# DAU-3Phase-PSU.net
KiCad netlist of a schematic drawn in Altium Designer
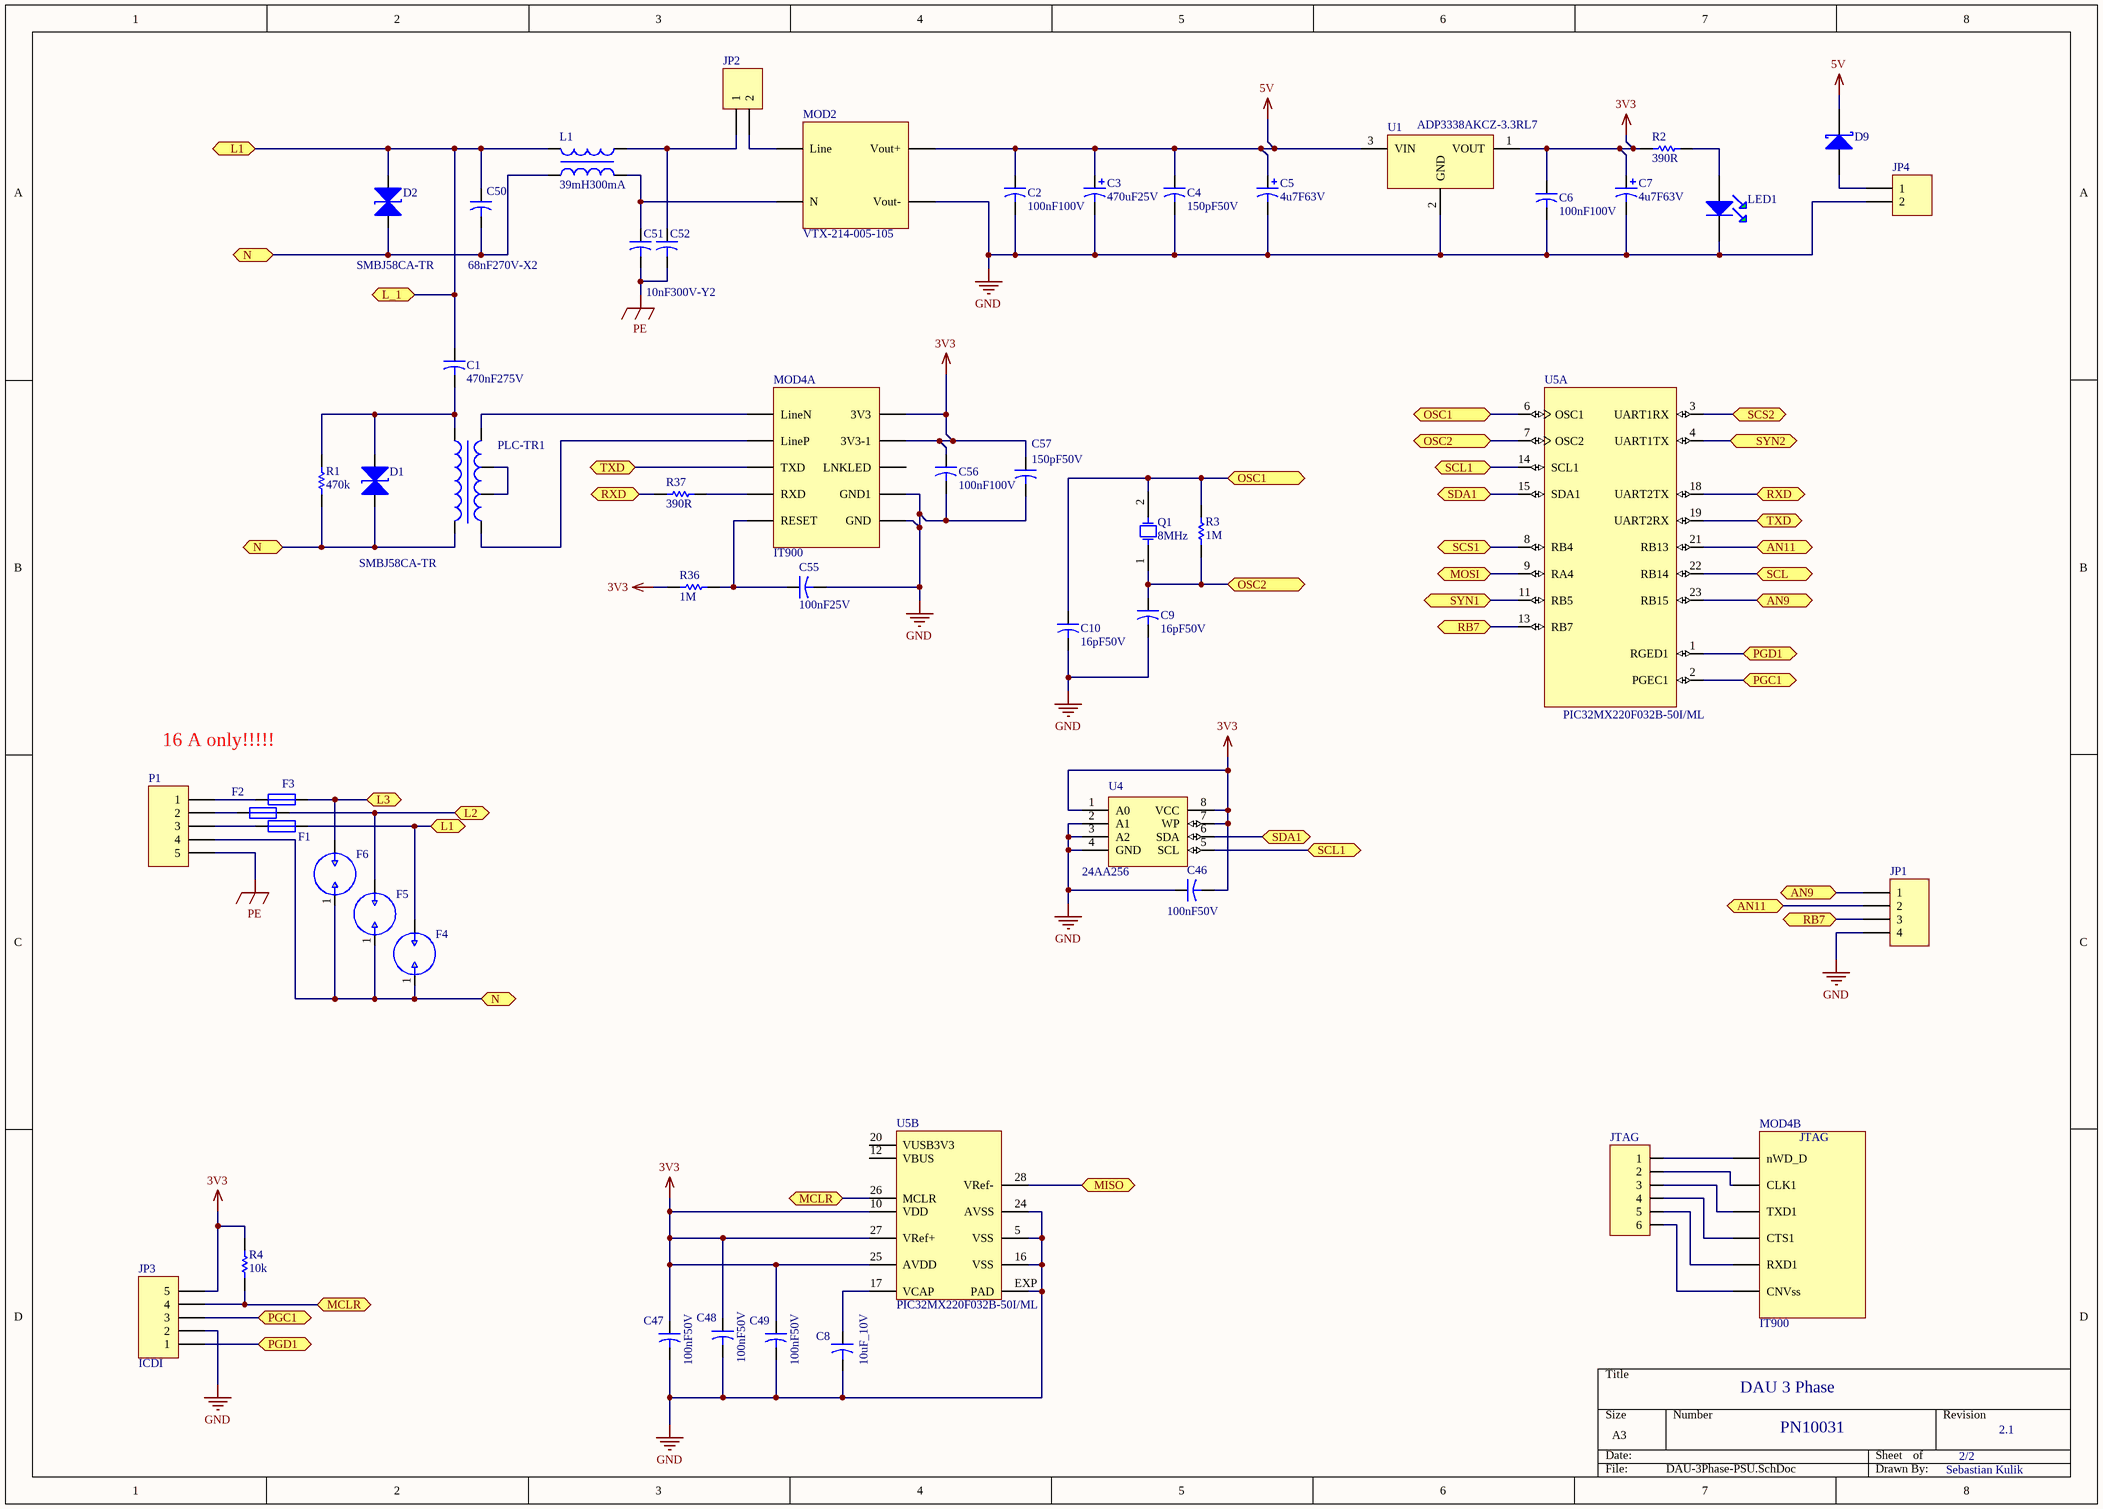
[diagram p0: DAU-3Phase-PSU.SchDoc]

(export (version "E")
  (design (tool "Eeschema 10.0.6"))
  (components
    (comp (ref "C1")
      (value "470nF275V")
      (footprint "C150-072X183")
      (description "X2, PP")
      (fields (field (name "MANUFACTURER") "WE") (field (name "PUBLISHER") "Sebastian Kulik"))
      (libsource (lib "Capacitors") (part "470nF275V"))
    )
    (comp (ref "C2")
      (value "100nF100V")
      (footprint "C0805")
      (description "AVX, X7R, 5%, 100V")
      (fields
        (field (name "MANUFACTURER") "AVX")
        (field (name "Comment") "100nF100V_0805")
        (field (name "PUBLISHER") "Sebastian Kulik")
      )
      (libsource (lib "Capacitors") (part "100nF100V_0805"))
    )
    (comp (ref "C3")
      (value "470uF25V")
      (footprint "Panasonic-FT-F_Case")
      (description "Panasonic, FT series")
      (fields
        (field (name "MANUFACTURER") "Panasonic")
        (field (name "Comment") "470uF25V_POL_FT")
        (field (name "PUBLISHER") "Sebastian Kulik")
      )
      (libsource (lib "Capacitors") (part "470uF25V_POL_FT"))
    )
    (comp (ref "C4")
      (value "150pF50V")
      (footprint "C0402")
      (description "C series, 5%, 50V")
      (fields
        (field (name "MANUFACTURER") "Murata")
        (field (name "Comment") "150p50V_0402")
        (field (name "PUBLISHER") "Sebastian Kulik")
      )
      (libsource (lib "") (part "150p50V_0402_1"))
    )
    (comp (ref "C5")
      (value "4u7F63V")
      (footprint "Panasonic-FT-C_Case")
      (description "Panasonic, TK series")
      (fields
        (field (name "MANUFACTURER") "Panasonic")
        (field (name "Comment") "4u7F25V_POL_TK")
        (field (name "PUBLISHER") "Sebastian Kulik")
      )
      (libsource (lib "Capacitors") (part "4u7F25V_POL_TK"))
    )
    (comp (ref "C6")
      (value "100nF100V")
      (footprint "C0805")
      (description "AVX, X7R, 5%, 100V")
      (fields
        (field (name "MANUFACTURER") "AVX")
        (field (name "Comment") "100nF100V_0805")
        (field (name "PUBLISHER") "Sebastian Kulik")
      )
      (libsource (lib "") (part "100nF100V_0805_1"))
    )
    (comp (ref "C7")
      (value "4u7F63V")
      (footprint "Panasonic-FT-C_Case")
      (description "Panasonic, TK series")
      (fields
        (field (name "MANUFACTURER") "Panasonic")
        (field (name "Comment") "4u7F25V_POL_TK")
        (field (name "PUBLISHER") "Sebastian Kulik")
      )
      (libsource (lib "Capacitors") (part "4u7F25V_POL_TK"))
    )
    (comp (ref "C8")
      (value "10uF_10V")
      (footprint "C0603")
      (description "AVX ,  X5R, 20%, 10V")
      (fields
        (field (name "MANUFACTURER") "AVX")
        (field (name "Comment") "10uF10V_0603")
        (field (name "PUBLISHER") "Sebastian Kulik")
      )
      (libsource (lib "Capacitors") (part "10uF10V_0603"))
    )
    (comp (ref "C9")
      (value "16pF50V")
      (footprint "C0402")
      (description "C series, 5%, 50V")
      (fields
        (field (name "MANUFACTURER") "Kemet")
        (field (name "Comment") "16pF50V_0402")
        (field (name "PUBLISHER") "Sebastian Kulik")
      )
      (libsource (lib "Capacitors") (part "16pF50V_0402"))
    )
    (comp (ref "C10")
      (value "16pF50V")
      (footprint "C0402")
      (description "C series, 5%, 50V")
      (fields
        (field (name "MANUFACTURER") "Kemet")
        (field (name "Comment") "16pF50V_0402")
        (field (name "PUBLISHER") "Sebastian Kulik")
      )
      (libsource (lib "Capacitors") (part "16pF50V_0402"))
    )
    (comp (ref "C46")
      (value "100nF50V")
      (footprint "C0402")
      (description "C series, X5R, 10%, 50V")
      (fields
        (field (name "MANUFACTURER") "Murata")
        (field (name "Comment") "100n50V_0402")
        (field (name "PUBLISHER") "Sebastian Kulik")
      )
      (libsource (lib "Capacitors") (part "100n50V_0402"))
    )
    (comp (ref "C47")
      (value "100nF50V")
      (footprint "C0402")
      (description "C series, X5R, 10%, 50V")
      (fields
        (field (name "MANUFACTURER") "Murata")
        (field (name "Comment") "100n50V_0402")
        (field (name "PUBLISHER") "Sebastian Kulik")
      )
      (libsource (lib "Capacitors") (part "100n50V_0402"))
    )
    (comp (ref "C48")
      (value "100nF50V")
      (footprint "C0402")
      (description "C series, X5R, 10%, 50V")
      (fields
        (field (name "MANUFACTURER") "Murata")
        (field (name "Comment") "100n50V_0402")
        (field (name "PUBLISHER") "Sebastian Kulik")
      )
      (libsource (lib "Capacitors") (part "100n50V_0402"))
    )
    (comp (ref "C49")
      (value "100nF50V")
      (footprint "C0402")
      (description "C series, X5R, 10%, 50V")
      (fields
        (field (name "MANUFACTURER") "Murata")
        (field (name "Comment") "100n50V_0402")
        (field (name "PUBLISHER") "Sebastian Kulik")
      )
      (libsource (lib "Capacitors") (part "100n50V_0402"))
    )
    (comp (ref "C50")
      (value "68nF270V-X2")
      (footprint "Foil-7,5x10")
      (description "X2 capacitor")
      (fields (field (name "MANUFACTURER") "WE") (field (name "PUBLISHER") "Sebastian Kulik"))
      (libsource (lib "Capacitors") (part "68nF270V-X2"))
    )
    (comp (ref "C51")
      (value "10nF300V-Y2")
      (footprint "Foil-10x13")
      (description "Y2 capacitor")
      (fields (field (name "MANUFACTURER") "EPCOS") (field (name "PUBLISHER") "Sebastian Kulik"))
      (libsource (lib "Capacitors") (part "10nF300V-Y2"))
    )
    (comp (ref "C52")
      (value "10nF300V-Y2")
      (footprint "Foil-10x13")
      (description "Y2 capacitor")
      (fields (field (name "MANUFACTURER") "EPCOS") (field (name "PUBLISHER") "Sebastian Kulik"))
      (libsource (lib "Capacitors") (part "10nF300V-Y2"))
    )
    (comp (ref "C55")
      (value "100nF25V")
      (footprint "C0402")
      (description "AVX, X5R, 10%, 25V")
      (fields
        (field (name "MANUFACTURER") "AVX")
        (field (name "Comment") "100nF25V_0402")
        (field (name "PUBLISHER") "Sebastian Kulik")
      )
      (libsource (lib "Capacitors") (part "100nF25V_0402"))
    )
    (comp (ref "C56")
      (value "100nF100V")
      (footprint "C0805")
      (description "AVX, X7R, 5%, 100V")
      (fields
        (field (name "MANUFACTURER") "AVX")
        (field (name "Comment") "100nF100V_0805")
        (field (name "PUBLISHER") "Sebastian Kulik")
      )
      (libsource (lib "") (part "100nF100V_0805_1"))
    )
    (comp (ref "C57")
      (value "150pF50V")
      (footprint "C0402")
      (description "C series, 5%, 50V")
      (fields
        (field (name "MANUFACTURER") "Murata")
        (field (name "Comment") "150p50V_0402")
        (field (name "PUBLISHER") "Sebastian Kulik")
      )
      (libsource (lib "Capacitors") (part "150p50V_0402"))
    )
    (comp (ref "D1")
      (value "SMBJ58CA-TR")
      (footprint "SMB")
      (description "Transient voltage suppressor, 600W")
      (fields (field (name "MANUFACTURER") "STMicro") (field (name "PUBLISHER") "Sebastian Kulik"))
      (libsource (lib "") (part "SMBJ58CA-TR_1"))
    )
    (comp (ref "D2")
      (value "SMBJ58CA-TR")
      (footprint "SMB")
      (description "Transient voltage suppressor, 600W")
      (fields (field (name "MANUFACTURER") "STMicro") (field (name "PUBLISHER") "Sebastian Kulik"))
      (libsource (lib "Discrete") (part "SMBJ58CA-TR"))
    )
    (comp (ref "D9")
      (value "RB160M-30TR")
      (footprint "SOD123")
      (description "Diode Schottky,2A,40V")
      (fields (field (name "MANUFACTURER") "Rohm") (field (name "PUBLISHER") "Sebastian Kulik"))
      (libsource (lib "Discrete") (part "RB160M-30TR"))
    )
    (comp (ref "F1")
      (value "MCMET 250MA 250V")
      (footprint "TR5")
      (fields (field (name "MANUFACTURER") "Multicomp") (field (name "PUBLISHER") "Sebastian Kulik"))
      (libsource (lib "Mechanical") (part "MCMET 250MA 250V"))
    )
    (comp (ref "F2")
      (value "MCMET 250MA 250V")
      (footprint "TR5")
      (fields (field (name "MANUFACTURER") "Multicomp") (field (name "PUBLISHER") "Sebastian Kulik"))
      (libsource (lib "Mechanical") (part "MCMET 250MA 250V"))
    )
    (comp (ref "F3")
      (value "MCMET 250MA 250V")
      (footprint "TR5")
      (fields (field (name "MANUFACTURER") "Multicomp") (field (name "PUBLISHER") "Sebastian Kulik"))
      (libsource (lib "Mechanical") (part "MCMET 250MA 250V"))
    )
    (comp (ref "F4")
      (value "GDT-SL1011A-1")
      (footprint "SL1011A/SL1011B")
      (description "surge protector")
      (fields (field (name "MANUFACTURER") "LITTLEFUSE") (field (name "PUBLISHER") "Sebastian Kulik"))
      (libsource (lib "Passives") (part "GDT-SL1011A-1"))
    )
    (comp (ref "F5")
      (value "GDT-SL1011A-1")
      (footprint "SL1011A/SL1011B")
      (description "surge protector")
      (fields (field (name "MANUFACTURER") "LITTLEFUSE") (field (name "PUBLISHER") "Sebastian Kulik"))
      (libsource (lib "Passives") (part "GDT-SL1011A-1"))
    )
    (comp (ref "F6")
      (value "GDT-SL1011A-1")
      (footprint "SL1011A/SL1011B")
      (description "surge protector")
      (fields (field (name "MANUFACTURER") "LITTLEFUSE") (field (name "PUBLISHER") "Sebastian Kulik"))
      (libsource (lib "Passives") (part "GDT-SL1011A-1"))
    )
    (comp (ref "JP1")
      (value "Plug_4_90_2.54")
      (footprint "HDR1X4")
      (description "Plug, 4-Pin")
      (fields (field (name "MANUFACTURER") "WE") (field (name "PUBLISHER") "Sebastian Kulik"))
      (libsource (lib "Connectors") (part "Plug_4_90_2.54"))
    )
    (comp (ref "JP2")
      (value "Header-2")
      (footprint "HDR1X2")
      (description "Header, 2-Pin")
      (fields (field (name "PUBLISHER") "Sebastian Kulik"))
      (libsource (lib "Connectors") (part "Header-2"))
    )
    (comp (ref "JP3")
      (value "ICDI")
      (footprint "HDR1X5-1.27")
      (description "Header, 5-Pin")
      (fields (field (name "PUBLISHER") "Sebastian Kulik"))
      (libsource (lib "Connectors") (part "ICDI"))
    )
    (comp (ref "JP4")
      (value "Header-2")
      (footprint "HDR1X2")
      (description "Header, 2-Pin")
      (fields (field (name "PUBLISHER") "Sebastian Kulik"))
      (libsource (lib "") (part "Header-2_1"))
    )
    (comp (ref "JTAG")
      (value "JTAG")
      (footprint "HDR1X6-1.27")
      (description "Header, 6-Pin")
      (fields (field (name "PUBLISHER") "Sebastian Kulik"))
      (libsource (lib "Connectors") (part "ICDI_1"))
    )
    (comp (ref "L1")
      (value "39mH300mA")
      (footprint "WE-CMB-XS")
      (description "Power choke/EMC filter")
      (fields
        (field (name "MANUFACTURER") "WE")
        (field (name "Comment") "PowerChoke-2")
        (field (name "PUBLISHER") "Sebastian Kulik")
      )
      (libsource (lib "Passives") (part "PowerChoke-1_2"))
    )
    (comp (ref "LED1")
      (value "WL-SMCW-GREEN")
      (footprint "WE-0603")
      (description "LED, 0603, green")
      (fields (field (name "MANUFACTURER") "WE") (field (name "PUBLISHER") "Sebastian Kulik"))
      (libsource (lib "Discrete") (part "WL-SMCW-GREEN"))
    )
    (comp (ref "MOD2")
      (value "VTX-214-005-105")
      (footprint "VTX-214-005-105")
      (description "PSU module")
      (fields (field (name "MANUFACTURER") "VIGORTRONIX") (field (name "PUBLISHER") "Sebastian Kulik"))
      (libsource (lib "Modules") (part "VTX-214-005-105"))
    )
    (comp (ref "MOD4")
      (value "IT900")
      (footprint "IT900-PIM")
      (description "RMS converter")
      (fields (field (name "MANUFACTURER") "TDE") (field (name "PUBLISHER") "Sebastian Kulik"))
      (libsource (lib "Modules") (part "IT900"))
    )
    (comp (ref "P1")
      (value "Plug_05_5mm")
      (footprint "CONNECTOR_5_POL-5mm")
      (description "Plug, 08-Pin")
      (fields (field (name "MANUFACTURER") "Phoenix Contact") (field (name "PUBLISHER") "Sebastian Kulik"))
      (libsource (lib "Connectors") (part "Plug_05_5mm"))
    )
    (comp (ref "PLC-TR1")
      (value "PLC-Transformer")
      (footprint "PLC-UEBERTRAGER_V2")
      (fields (field (name "MANUFACTURER") "VAC") (field (name "PUBLISHER") "Sebastian Kulik"))
      (libsource (lib "Passives") (part "PLC-Transformer"))
    )
    (comp (ref "Q1")
      (value "8MHz")
      (footprint "ABM3")
      (description "Crystal, ABM3-8.000MHZ-D2Y-T")
      (fields
        (field (name "MANUFACTURER") "Abacon")
        (field (name "Comment") "Crystal_8MHz_1")
        (field (name "PUBLISHER") "Sebastian Kulik")
      )
      (libsource (lib "Passives") (part "Crystal_8MHz_1"))
    )
    (comp (ref "R1")
      (value "470k")
      (footprint "0204/7")
      (description "MRS25 series, 1%, 600mW")
      (fields
        (field (name "MANUFACTURER") "Vishay")
        (field (name "Comment") "470k_0204/7")
        (field (name "PUBLISHER") "Sebastian Kulik")
      )
      (libsource (lib "Resistors") (part "470k_0204/7"))
    )
    (comp (ref "R2")
      (value "390R")
      (footprint "R0402")
      (description "CRCW series, 125mW, 1%")
      (fields
        (field (name "MANUFACTURER") "Vishay")
        (field (name "Comment") "390R_0402")
        (field (name "PUBLISHER") "Sebastian Kulik")
      )
      (libsource (lib "Resistors") (part "390R_0402"))
    )
    (comp (ref "R3")
      (value "1M")
      (footprint "R0402")
      (description "Vishay CRCW series, 64mW, 1%")
      (fields
        (field (name "MANUFACTURER") "Vishay")
        (field (name "Comment") "1M_0402")
        (field (name "PUBLISHER") "Sebastian Kulik")
      )
      (libsource (lib "Resistors") (part "1M_0402"))
    )
    (comp (ref "R4")
      (value "10k")
      (footprint "R0402")
      (description "Vishay CRCW series, 125mW, 1%")
      (fields
        (field (name "MANUFACTURER") "Vishay")
        (field (name "Comment") "10k_0402")
        (field (name "PUBLISHER") "Sebastian Kulik")
      )
      (libsource (lib "Resistors") (part "10k_0402"))
    )
    (comp (ref "R36")
      (value "1M")
      (footprint "R0402")
      (description "Vishay CRCW series, 64mW, 1%")
      (fields
        (field (name "MANUFACTURER") "Vishay")
        (field (name "Comment") "1M_0402")
        (field (name "PUBLISHER") "Sebastian Kulik")
      )
      (libsource (lib "Resistors") (part "1M_0402"))
    )
    (comp (ref "R37")
      (value "390R")
      (footprint "R0402")
      (description "CRCW series, 125mW, 1%")
      (fields
        (field (name "MANUFACTURER") "Vishay")
        (field (name "Comment") "390R_0402")
        (field (name "PUBLISHER") "Sebastian Kulik")
      )
      (libsource (lib "Resistors") (part "390R_0402"))
    )
    (comp (ref "U1")
      (value "ADP3338AKCZ-3.3RL7")
      (footprint "SOT223-1")
      (description "LDO, 3V3_1A")
      (fields (field (name "MANUFACTURER") "ADI") (field (name "PUBLISHER") "Sebastian Kulik"))
      (libsource (lib "ICs") (part "ADP3338AKCZ-3.3RL7"))
    )
    (comp (ref "U4")
      (value "24AA256")
      (footprint "TSSOP8")
      (description "I2C  EEPROM")
      (fields (field (name "MANUFACTURER") "Microchip") (field (name "PUBLISHER") "Sebastian Kulik"))
      (libsource (lib "ICs") (part "24AA256"))
    )
    (comp (ref "U5")
      (value "PIC32MX220F032B-50I/ML")
      (footprint "QFN28_LONG_ERRLES-Vias")
      (description "High Performance ROM-less Microcontroller")
      (fields (field (name "MANUFACTURER") "Microchip") (field (name "PUBLISHER") "Sebastian Kulik"))
      (libsource (lib "ICs") (part "PIC32MX220F032B-50I/ML"))
    )
  )
  (nets
    (net (code "1") (name "/AN9") (class "Default")
      (node (ref "JP1") (pin "1") (pinfunction "1_1") (pintype "passive"))
      (node (ref "U5") (pin "23") (pinfunction "RB15_23") (pintype "bidirectional"))
    )
    (net (code "2") (name "/AN11") (class "Default")
      (node (ref "JP1") (pin "2") (pinfunction "2_2") (pintype "passive"))
      (node (ref "U5") (pin "21") (pinfunction "RB13_21") (pintype "bidirectional"))
    )
    (net (code "3") (name "/L1") (class "Default")
      (node (ref "C1") (pin "1") (pinfunction "1_1") (pintype "passive"))
      (node (ref "C50") (pin "1") (pinfunction "1_1") (pintype "passive"))
      (node (ref "D2") (pin "2") (pinfunction "A_2") (pintype "passive"))
      (node (ref "F1") (pin "2") (pinfunction "2_2") (pintype "passive"))
      (node (ref "F4") (pin "2") (pinfunction "2_2") (pintype "passive"))
      (node (ref "L1") (pin "2") (pinfunction "2_2") (pintype "passive"))
    )
    (net (code "4") (name "/L2") (class "Default")
      (node (ref "F2") (pin "2") (pinfunction "2_2") (pintype "passive"))
      (node (ref "F5") (pin "2") (pinfunction "2_2") (pintype "passive"))
    )
    (net (code "5") (name "/L3") (class "Default")
      (node (ref "F3") (pin "2") (pinfunction "2_2") (pintype "passive"))
      (node (ref "F6") (pin "2") (pinfunction "2_2") (pintype "passive"))
    )
    (net (code "6") (name "/MCLR") (class "Default")
      (node (ref "JP3") (pin "4") (pinfunction "4_4") (pintype "passive"))
      (node (ref "R4") (pin "1") (pinfunction "1_1") (pintype "passive"))
      (node (ref "U5") (pin "26") (pinfunction "MCLR_26") (pintype "passive"))
    )
    (net (code "7") (name "/MISO") (class "Default")
      (node (ref "U5") (pin "28") (pinfunction "VRef-_28") (pintype "power_in"))
    )
    (net (code "8") (name "/MOSI") (class "Default")
      (node (ref "U5") (pin "9") (pinfunction "RA4_9") (pintype "bidirectional"))
    )
    (net (code "9") (name "/N") (class "Default")
      (node (ref "C50") (pin "2") (pinfunction "2_2") (pintype "passive"))
      (node (ref "D1") (pin "1") (pinfunction "K_1") (pintype "passive"))
      (node (ref "D2") (pin "1") (pinfunction "K_1") (pintype "passive"))
      (node (ref "F4") (pin "1") (pinfunction "1_1") (pintype "passive"))
      (node (ref "F5") (pin "1") (pinfunction "1_1") (pintype "passive"))
      (node (ref "F6") (pin "1") (pinfunction "1_1") (pintype "passive"))
      (node (ref "L1") (pin "1") (pinfunction "1_1") (pintype "passive"))
      (node (ref "P1") (pin "4") (pinfunction "4_4") (pintype "passive"))
      (node (ref "PLC-TR1") (pin "8N") (pinfunction "8N_8N") (pintype "passive"))
      (node (ref "R1") (pin "1") (pinfunction "1_1") (pintype "passive"))
    )
    (net (code "10") (name "/OSC1") (class "Default")
      (node (ref "C10") (pin "1") (pinfunction "1_1") (pintype "passive"))
      (node (ref "Q1") (pin "2") (pinfunction "2_2") (pintype "passive"))
      (node (ref "R3") (pin "2") (pinfunction "2_2") (pintype "passive"))
      (node (ref "U5") (pin "6") (pinfunction "OSC1_6") (pintype "bidirectional"))
    )
    (net (code "11") (name "/OSC2") (class "Default")
      (node (ref "C9") (pin "1") (pinfunction "1_1") (pintype "passive"))
      (node (ref "Q1") (pin "1") (pinfunction "1_1") (pintype "passive"))
      (node (ref "R3") (pin "1") (pinfunction "1_1") (pintype "passive"))
      (node (ref "U5") (pin "7") (pinfunction "OSC2_7") (pintype "bidirectional"))
    )
    (net (code "12") (name "/PGC1") (class "Default")
      (node (ref "JP3") (pin "3") (pinfunction "3_3") (pintype "passive"))
      (node (ref "U5") (pin "2") (pinfunction "PGEC1_2") (pintype "bidirectional"))
    )
    (net (code "13") (name "/PGD1") (class "Default")
      (node (ref "JP3") (pin "1") (pinfunction "1_1") (pintype "passive"))
      (node (ref "U5") (pin "1") (pinfunction "RGED1_1") (pintype "bidirectional"))
    )
    (net (code "14") (name "/RB7") (class "Default")
      (node (ref "JP1") (pin "3") (pinfunction "3_3") (pintype "passive"))
      (node (ref "U5") (pin "13") (pinfunction "RB7_13") (pintype "bidirectional"))
    )
    (net (code "15") (name "/RXD") (class "Default")
      (node (ref "R37") (pin "1") (pinfunction "1_1") (pintype "passive"))
      (node (ref "U5") (pin "18") (pinfunction "UART2TX_18") (pintype "bidirectional"))
    )
    (net (code "16") (name "/SCL") (class "Default")
      (node (ref "U5") (pin "22") (pinfunction "RB14_22") (pintype "bidirectional"))
    )
    (net (code "17") (name "/SCL1") (class "Default")
      (node (ref "U4") (pin "5") (pinfunction "SCL_5") (pintype "bidirectional"))
      (node (ref "U5") (pin "14") (pinfunction "SCL1_14") (pintype "bidirectional"))
    )
    (net (code "18") (name "/SCS1") (class "Default")
      (node (ref "U5") (pin "8") (pinfunction "RB4_8") (pintype "bidirectional"))
    )
    (net (code "19") (name "/SCS2") (class "Default")
      (node (ref "U5") (pin "3") (pinfunction "UART1RX_3") (pintype "bidirectional"))
    )
    (net (code "20") (name "/SDA1") (class "Default")
      (node (ref "U4") (pin "6") (pinfunction "SDA_6") (pintype "bidirectional"))
      (node (ref "U5") (pin "15") (pinfunction "SDA1_15") (pintype "bidirectional"))
    )
    (net (code "21") (name "/SYN1") (class "Default")
      (node (ref "U5") (pin "11") (pinfunction "RB5_11") (pintype "bidirectional"))
    )
    (net (code "22") (name "/SYN2") (class "Default")
      (node (ref "U5") (pin "4") (pinfunction "UART1TX_4") (pintype "bidirectional"))
    )
    (net (code "23") (name "/TXD") (class "Default")
      (node (ref "MOD4") (pin "16") (pinfunction "TXD_16") (pintype "passive"))
      (node (ref "U5") (pin "19") (pinfunction "UART2RX_19") (pintype "bidirectional"))
    )
    (net (code "24") (name "3V3") (class "Default")
      (node (ref "C46") (pin "2") (pinfunction "2_2") (pintype "passive"))
      (node (ref "C47") (pin "1") (pinfunction "1_1") (pintype "passive"))
      (node (ref "C48") (pin "1") (pinfunction "1_1") (pintype "passive"))
      (node (ref "C49") (pin "1") (pinfunction "1_1") (pintype "passive"))
      (node (ref "C56") (pin "1") (pinfunction "1_1") (pintype "passive"))
      (node (ref "C57") (pin "1") (pinfunction "1_1") (pintype "passive"))
      (node (ref "C6") (pin "1") (pinfunction "1_1") (pintype "passive"))
      (node (ref "C7") (pin "1") (pinfunction "1_1") (pintype "passive"))
      (node (ref "JP3") (pin "5") (pinfunction "5_5") (pintype "passive"))
      (node (ref "MOD4") (pin "4") (pinfunction "3V3_4") (pintype "passive"))
      (node (ref "MOD4") (pin "5") (pinfunction "3V3-1_5") (pintype "passive"))
      (node (ref "R2") (pin "1") (pinfunction "1_1") (pintype "passive"))
      (node (ref "R36") (pin "1") (pinfunction "1_1") (pintype "passive"))
      (node (ref "R4") (pin "2") (pinfunction "2_2") (pintype "passive"))
      (node (ref "U1") (pin "1") (pinfunction "VOUT_1") (pintype "passive"))
      (node (ref "U4") (pin "1") (pinfunction "A0_1") (pintype "passive"))
      (node (ref "U4") (pin "7") (pinfunction "WP_7") (pintype "bidirectional"))
      (node (ref "U4") (pin "8") (pinfunction "VCC_8") (pintype "power_in"))
      (node (ref "U5") (pin "10") (pinfunction "VDD_10") (pintype "power_in"))
      (node (ref "U5") (pin "25") (pinfunction "AVDD_25") (pintype "power_in"))
      (node (ref "U5") (pin "27") (pinfunction "VRef+_27") (pintype "power_in"))
    )
    (net (code "25") (name "5V") (class "Default")
      (node (ref "C2") (pin "1") (pinfunction "1_1") (pintype "passive"))
      (node (ref "C3") (pin "1") (pinfunction "1_1") (pintype "passive"))
      (node (ref "C4") (pin "1") (pinfunction "1_1") (pintype "passive"))
      (node (ref "C5") (pin "1") (pinfunction "1_1") (pintype "passive"))
      (node (ref "D9") (pin "1") (pinfunction "K_1") (pintype "passive"))
      (node (ref "MOD2") (pin "+VO") (pinfunction "Vout+_+VO") (pintype "passive"))
      (node (ref "U1") (pin "3") (pinfunction "VIN_3") (pintype "passive"))
    )
    (net (code "26") (name "GND") (class "Default")
      (node (ref "C10") (pin "2") (pinfunction "2_2") (pintype "passive"))
      (node (ref "C2") (pin "2") (pinfunction "2_2") (pintype "passive"))
      (node (ref "C3") (pin "2") (pinfunction "2_2") (pintype "passive"))
      (node (ref "C4") (pin "2") (pinfunction "2_2") (pintype "passive"))
      (node (ref "C46") (pin "1") (pinfunction "1_1") (pintype "passive"))
      (node (ref "C47") (pin "2") (pinfunction "2_2") (pintype "passive"))
      (node (ref "C48") (pin "2") (pinfunction "2_2") (pintype "passive"))
      (node (ref "C49") (pin "2") (pinfunction "2_2") (pintype "passive"))
      (node (ref "C5") (pin "2") (pinfunction "2_2") (pintype "passive"))
      (node (ref "C55") (pin "2") (pinfunction "2_2") (pintype "passive"))
      (node (ref "C56") (pin "2") (pinfunction "2_2") (pintype "passive"))
      (node (ref "C57") (pin "2") (pinfunction "2_2") (pintype "passive"))
      (node (ref "C6") (pin "2") (pinfunction "2_2") (pintype "passive"))
      (node (ref "C7") (pin "2") (pinfunction "2_2") (pintype "passive"))
      (node (ref "C8") (pin "2") (pinfunction "2_2") (pintype "passive"))
      (node (ref "C9") (pin "2") (pinfunction "2_2") (pintype "passive"))
      (node (ref "JP1") (pin "4") (pinfunction "4_4") (pintype "passive"))
      (node (ref "JP3") (pin "2") (pinfunction "2_2") (pintype "passive"))
      (node (ref "JP4") (pin "2") (pinfunction "2_2") (pintype "passive"))
      (node (ref "LED1") (pin "1") (pinfunction "K_1") (pintype "passive"))
      (node (ref "MOD2") (pin "-VO") (pinfunction "Vout-_-VO") (pintype "passive"))
      (node (ref "MOD4") (pin "2") (pinfunction "GND_2") (pintype "passive"))
      (node (ref "MOD4") (pin "3") (pinfunction "GND1_3") (pintype "passive"))
      (node (ref "U1") (pin "2") (pinfunction "GND_2") (pintype "passive"))
      (node (ref "U4") (pin "2") (pinfunction "A1_2") (pintype "passive"))
      (node (ref "U4") (pin "3") (pinfunction "A2_3") (pintype "passive"))
      (node (ref "U4") (pin "4") (pinfunction "GND_4") (pintype "power_in"))
      (node (ref "U5") (pin "16") (pinfunction "VSS_16") (pintype "power_in"))
      (node (ref "U5") (pin "24") (pinfunction "AVSS_24") (pintype "power_in"))
      (node (ref "U5") (pin "5") (pinfunction "VSS_5") (pintype "power_in"))
      (node (ref "U5") (pin "EXP") (pinfunction "PAD_EXP") (pintype "power_in"))
    )
    (net (code "27") (name "Net-(C51-Pad1)") (class "Default")
      (node (ref "C51") (pin "1") (pinfunction "1_1") (pintype "passive"))
      (node (ref "L1") (pin "4") (pinfunction "4_4") (pintype "passive"))
      (node (ref "MOD2") (pin "N") (pinfunction "N_N") (pintype "passive"))
    )
    (net (code "28") (name "Net-(C52-Pad1)") (class "Default")
      (node (ref "C52") (pin "1") (pinfunction "1_1") (pintype "passive"))
      (node (ref "JP2") (pin "1") (pinfunction "1_1") (pintype "passive"))
      (node (ref "L1") (pin "3") (pinfunction "3_3") (pintype "passive"))
    )
    (net (code "29") (name "Net-(D1-A)") (class "Default")
      (node (ref "C1") (pin "2") (pinfunction "2_2") (pintype "passive"))
      (node (ref "D1") (pin "2") (pinfunction "A_2") (pintype "passive"))
      (node (ref "PLC-TR1") (pin "L5") (pinfunction "L5_L5") (pintype "passive"))
      (node (ref "R1") (pin "2") (pinfunction "2_2") (pintype "passive"))
    )
    (net (code "30") (name "Net-(D9-A)") (class "Default")
      (node (ref "D9") (pin "2") (pinfunction "A_2") (pintype "passive"))
      (node (ref "JP4") (pin "1") (pinfunction "1_1") (pintype "passive"))
    )
    (net (code "31") (name "Net-(F1-Pad1)") (class "Default")
      (node (ref "F1") (pin "1") (pinfunction "1_1") (pintype "passive"))
      (node (ref "P1") (pin "3") (pinfunction "3_3") (pintype "passive"))
    )
    (net (code "32") (name "Net-(F2-Pad1)") (class "Default")
      (node (ref "F2") (pin "1") (pinfunction "1_1") (pintype "passive"))
      (node (ref "P1") (pin "2") (pinfunction "2_2") (pintype "passive"))
    )
    (net (code "33") (name "Net-(F3-Pad1)") (class "Default")
      (node (ref "F3") (pin "1") (pinfunction "1_1") (pintype "passive"))
      (node (ref "P1") (pin "1") (pinfunction "1_1") (pintype "passive"))
    )
    (net (code "34") (name "Net-(LED1-A)") (class "Default")
      (node (ref "LED1") (pin "2") (pinfunction "A_2") (pintype "passive"))
      (node (ref "R2") (pin "2") (pinfunction "2_2") (pintype "passive"))
    )
    (net (code "35") (name "Net-(MOD2-Line)") (class "Default")
      (node (ref "JP2") (pin "2") (pinfunction "2_2") (pintype "passive"))
      (node (ref "MOD2") (pin "L") (pinfunction "Line_L") (pintype "passive"))
    )
    (net (code "36") (name "Net-(MOD4A-LineN)") (class "Default")
      (node (ref "MOD4") (pin "20") (pinfunction "LineN_20") (pintype "passive"))
      (node (ref "PLC-TR1") (pin "1LINE1") (pinfunction "LINE1_1LINE1") (pintype "passive"))
    )
    (net (code "37") (name "Net-(MOD4A-LineP)") (class "Default")
      (node (ref "MOD4") (pin "21") (pinfunction "LineP_21") (pintype "passive"))
      (node (ref "PLC-TR1") (pin "4LINE2") (pinfunction "4LINE2_4LINE2") (pintype "passive"))
    )
    (net (code "38") (name "Net-(MOD4A-RESET)") (class "Default")
      (node (ref "C55") (pin "1") (pinfunction "1_1") (pintype "passive"))
      (node (ref "MOD4") (pin "9") (pinfunction "RESET_9") (pintype "passive"))
      (node (ref "R36") (pin "2") (pinfunction "2_2") (pintype "passive"))
    )
    (net (code "39") (name "Net-(MOD4A-RXD)") (class "Default")
      (node (ref "MOD4") (pin "17") (pinfunction "RXD_17") (pintype "passive"))
      (node (ref "R37") (pin "2") (pinfunction "2_2") (pintype "passive"))
    )
    (net (code "40") (name "Net-(MOD4B-CLK1)") (class "Default")
      (node (ref "JTAG") (pin "2") (pinfunction "2_2") (pintype "passive"))
      (node (ref "MOD4") (pin "27") (pinfunction "CLK1_27") (pintype "passive"))
    )
    (net (code "41") (name "Net-(MOD4B-CNVss)") (class "Default")
      (node (ref "JTAG") (pin "6") (pinfunction "6_6") (pintype "passive"))
      (node (ref "MOD4") (pin "31") (pinfunction "CNVss_31") (pintype "passive"))
    )
    (net (code "42") (name "Net-(MOD4B-CTS1)") (class "Default")
      (node (ref "JTAG") (pin "4") (pinfunction "4_4") (pintype "passive"))
      (node (ref "MOD4") (pin "29") (pinfunction "CTS1_29") (pintype "passive"))
    )
    (net (code "43") (name "Net-(MOD4B-RXD1)") (class "Default")
      (node (ref "JTAG") (pin "5") (pinfunction "5_5") (pintype "passive"))
      (node (ref "MOD4") (pin "30") (pinfunction "RXD1_30") (pintype "passive"))
    )
    (net (code "44") (name "Net-(MOD4B-TXD1)") (class "Default")
      (node (ref "JTAG") (pin "3") (pinfunction "3_3") (pintype "passive"))
      (node (ref "MOD4") (pin "28") (pinfunction "TXD1_28") (pintype "passive"))
    )
    (net (code "45") (name "Net-(MOD4B-nWD_D)") (class "Default")
      (node (ref "JTAG") (pin "1") (pinfunction "1_1") (pintype "passive"))
      (node (ref "MOD4") (pin "26") (pinfunction "nWD_D_26") (pintype "passive"))
    )
    (net (code "46") (name "Net-(PLC-TR1-Pad2)") (class "Default")
      (node (ref "PLC-TR1") (pin "2") (pinfunction "2_2") (pintype "passive"))
      (node (ref "PLC-TR1") (pin "3") (pinfunction "3_3") (pintype "passive"))
    )
    (net (code "47") (name "Net-(U5B-VCAP)") (class "Default")
      (node (ref "C8") (pin "1") (pinfunction "1_1") (pintype "passive"))
      (node (ref "U5") (pin "17") (pinfunction "VCAP_17") (pintype "power_in"))
    )
    (net (code "48") (name "PE") (class "Default")
      (node (ref "C51") (pin "2") (pinfunction "2_2") (pintype "passive"))
      (node (ref "C52") (pin "2") (pinfunction "2_2") (pintype "passive"))
      (node (ref "P1") (pin "5") (pinfunction "5_5") (pintype "passive"))
    )
    (net (code "49") (name "unconnected-(MOD4A-LNKLED-Pad22)") (class "Default")
      (node (ref "MOD4") (pin "22") (pinfunction "LNKLED_22") (pintype "passive"))
    )
    (net (code "50") (name "unconnected-(U5B-VBUS-Pad12)") (class "Default")
      (node (ref "U5") (pin "12") (pinfunction "VBUS_12") (pintype "power_in"))
    )
    (net (code "51") (name "unconnected-(U5B-VUSB3V3-Pad20)") (class "Default")
      (node (ref "U5") (pin "20") (pinfunction "VUSB3V3_20") (pintype "power_in"))
    )
  )
)
